# AK-Logger.net
KiCad netlist of a schematic drawn in EAGLE
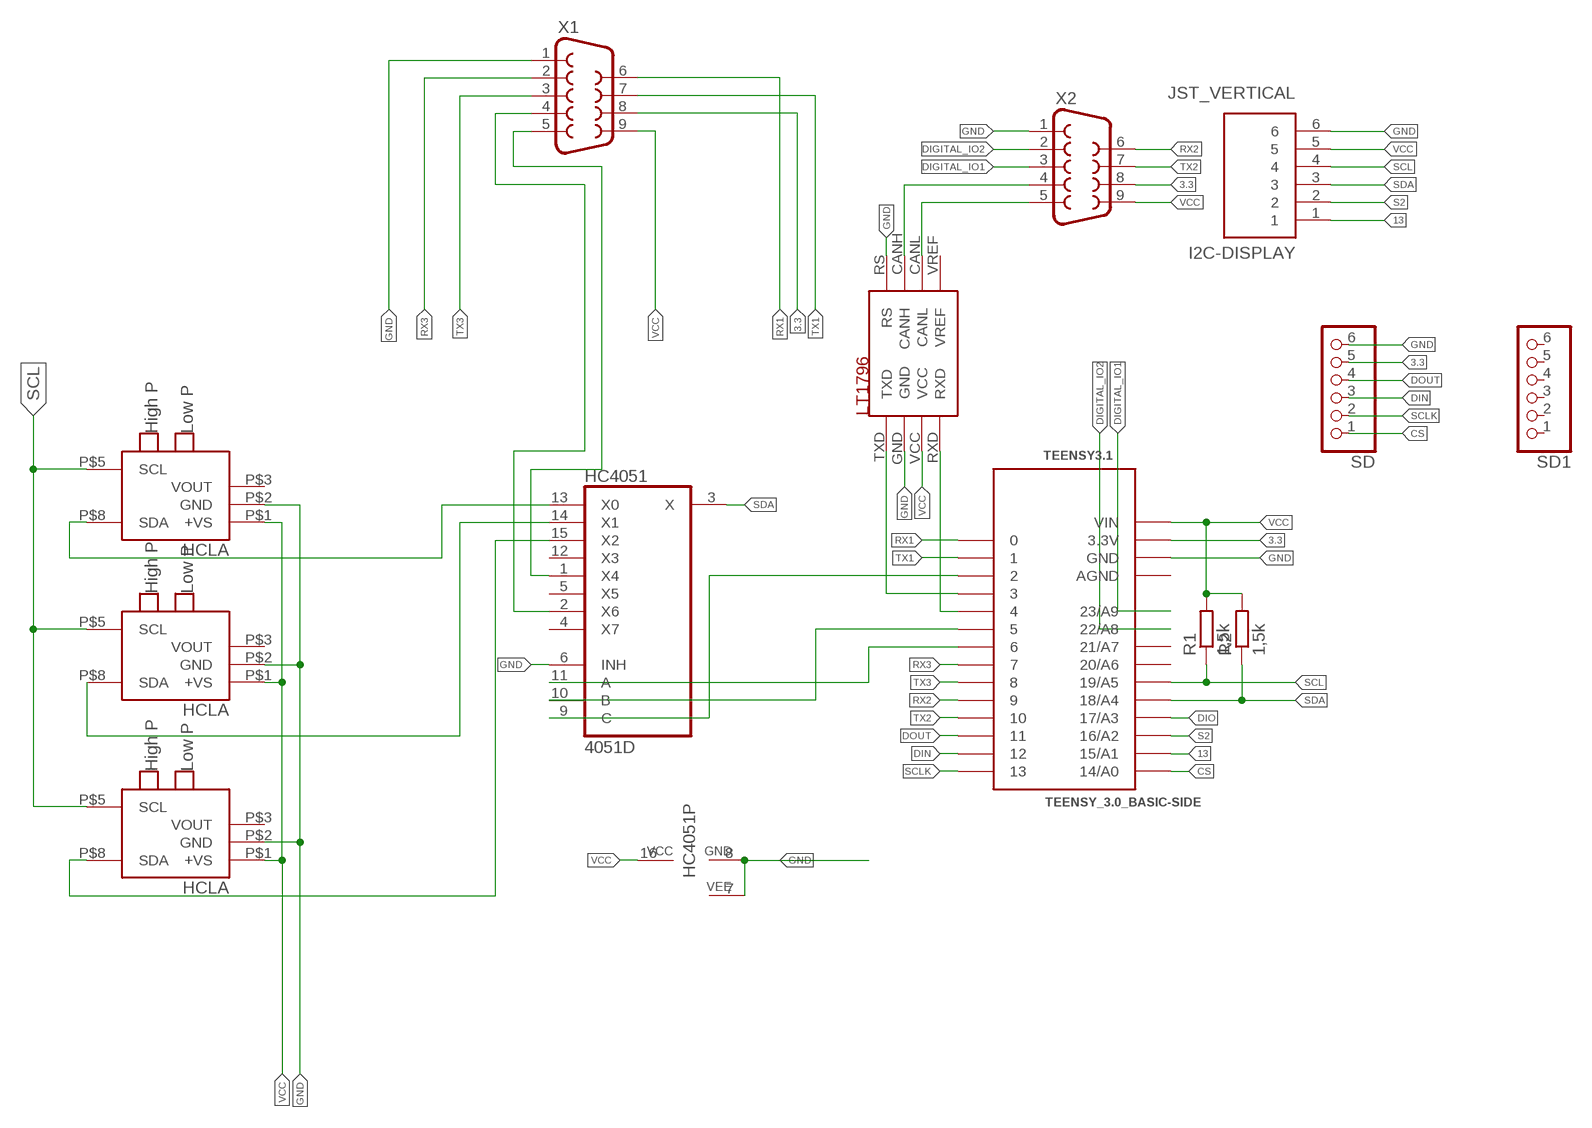
[diagram p0: schematic, sheet 1]

(export (version "E")
  (design (tool "Eeschema 10.0.6"))
  (components
    (comp (ref "HC4051")
      (value "4051D")
      (footprint "eagle-import:SO16")
      (libsource (lib "eagle-import") (part "4051D"))
    )
    (comp (ref "HCLA0")
      (value "HCLA")
      (footprint "eagle-import:HCLA")
      (libsource (lib "eagle-import") (part "HCLA"))
    )
    (comp (ref "HCLA1")
      (value "HCLA")
      (footprint "eagle-import:HCLA")
      (libsource (lib "eagle-import") (part "HCLA"))
    )
    (comp (ref "HCLA2")
      (value "HCLA")
      (footprint "eagle-import:HCLA")
      (libsource (lib "eagle-import") (part "HCLA"))
    )
    (comp (ref "I2C-DISPLAY")
      (value "JST_VERTICAL")
      (footprint "eagle-import:JST-6-SMD-VERT-1.0MM")
      (libsource (lib "eagle-import") (part "JST_VERTICAL"))
    )
    (comp (ref "R1")
      (value "1,5k")
      (footprint "eagle-import:R1206")
      (libsource (lib "eagle-import") (part "R-EU_R1206"))
    )
    (comp (ref "R2")
      (value "1,5k")
      (footprint "eagle-import:R1206")
      (libsource (lib "eagle-import") (part "R-EU_R1206"))
    )
    (comp (ref "SD")
      (value "PINHD-1X6")
      (footprint "eagle-import:1X06")
      (libsource (lib "eagle-import") (part "PINHD-1X6"))
    )
    (comp (ref "SD1")
      (value "PINHD-1X6")
      (footprint "eagle-import:1X06")
      (libsource (lib "eagle-import") (part "PINHD-1X6"))
    )
    (comp (ref "TEENSY3.1")
      (value "TEENSY_3.0_BASIC-SIDE")
      (footprint "eagle-import:TEENSY_3.0_BASIC-SIDE")
      (libsource (lib "eagle-import") (part "TEENSY_3.0_BASIC-SIDE"))
    )
    (comp (ref "U$6")
      (value "LT1796")
      (footprint "eagle-import:SO08")
      (libsource (lib "eagle-import") (part "LT1796"))
    )
    (comp (ref "X1")
      (value "F09H")
      (footprint "eagle-import:F09H")
      (libsource (lib "eagle-import") (part "F09H"))
    )
    (comp (ref "X2")
      (value "F09H")
      (footprint "eagle-import:F09H")
      (libsource (lib "eagle-import") (part "F09H"))
    )
  )
  (nets
    (net (code "1") (name "/AGND") (class "Default")
      (node (ref "TEENSY3.1") (pin "AGND") (pinfunction "AGND_AGND") (pintype "power_in"))
    )
    (net (code "2") (name "3.3") (class "Default")
      (node (ref "SD") (pin "5") (pinfunction "5_5") (pintype "passive"))
      (node (ref "TEENSY3.1") (pin "3.3V") (pinfunction "3.3V_3.3V") (pintype "power_in"))
      (node (ref "X1") (pin "8") (pinfunction "8_8") (pintype "passive"))
      (node (ref "X2") (pin "8") (pinfunction "8_8") (pintype "passive"))
    )
    (net (code "3") (name "13") (class "Default")
      (node (ref "I2C-DISPLAY") (pin "1") (pinfunction "1_1") (pintype "bidirectional"))
      (node (ref "TEENSY3.1") (pin "15/A1") (pinfunction "15/A1_15/A1") (pintype "bidirectional"))
    )
    (net (code "4") (name "CS") (class "Default")
      (node (ref "SD") (pin "1") (pinfunction "1_1") (pintype "passive"))
      (node (ref "TEENSY3.1") (pin "14/A0") (pinfunction "14/A0_14/A0") (pintype "bidirectional"))
    )
    (net (code "5") (name "DIGITAL_IO1") (class "Default")
      (node (ref "TEENSY3.1") (pin "23/A9") (pinfunction "23/A9_23/A9") (pintype "bidirectional"))
      (node (ref "X2") (pin "3") (pinfunction "3_3") (pintype "passive"))
    )
    (net (code "6") (name "DIGITAL_IO2") (class "Default")
      (node (ref "TEENSY3.1") (pin "22/A8") (pinfunction "22/A8_22/A8") (pintype "bidirectional"))
      (node (ref "X2") (pin "2") (pinfunction "2_2") (pintype "passive"))
    )
    (net (code "7") (name "DIN") (class "Default")
      (node (ref "SD") (pin "3") (pinfunction "3_3") (pintype "passive"))
      (node (ref "TEENSY3.1") (pin "12") (pinfunction "12_12") (pintype "bidirectional"))
    )
    (net (code "8") (name "DIO") (class "Default")
      (node (ref "TEENSY3.1") (pin "17/A3") (pinfunction "17/A3_17/A3") (pintype "bidirectional"))
    )
    (net (code "9") (name "DOUT") (class "Default")
      (node (ref "SD") (pin "4") (pinfunction "4_4") (pintype "passive"))
      (node (ref "TEENSY3.1") (pin "11") (pinfunction "11_11") (pintype "bidirectional"))
    )
    (net (code "10") (name "GND") (class "Default")
      (node (ref "HC4051") (pin "6") (pinfunction "INH_6") (pintype "input"))
      (node (ref "HC4051") (pin "7") (pinfunction "VEE_7") (pintype "power_in"))
      (node (ref "HC4051") (pin "8") (pinfunction "GND_8") (pintype "power_in"))
      (node (ref "HCLA0") (pin "P$2") (pinfunction "GND_P$2") (pintype "bidirectional"))
      (node (ref "HCLA1") (pin "P$2") (pinfunction "GND_P$2") (pintype "bidirectional"))
      (node (ref "HCLA2") (pin "P$2") (pinfunction "GND_P$2") (pintype "bidirectional"))
      (node (ref "I2C-DISPLAY") (pin "6") (pinfunction "6_6") (pintype "bidirectional"))
      (node (ref "SD") (pin "6") (pinfunction "6_6") (pintype "passive"))
      (node (ref "TEENSY3.1") (pin "GND") (pinfunction "GND_GND") (pintype "power_in"))
      (node (ref "U$6") (pin "GND") (pinfunction "GND_GND") (pintype "bidirectional"))
      (node (ref "U$6") (pin "RS") (pinfunction "RS_RS") (pintype "bidirectional"))
      (node (ref "X1") (pin "1") (pinfunction "1_1") (pintype "passive"))
      (node (ref "X2") (pin "1") (pinfunction "1_1") (pintype "passive"))
    )
    (net (code "11") (name "Net-(HC4051A-A)") (class "Default")
      (node (ref "HC4051") (pin "11") (pinfunction "A_11") (pintype "input"))
      (node (ref "TEENSY3.1") (pin "6") (pinfunction "6_6") (pintype "bidirectional"))
    )
    (net (code "12") (name "Net-(HC4051A-B)") (class "Default")
      (node (ref "HC4051") (pin "10") (pinfunction "B_10") (pintype "input"))
      (node (ref "TEENSY3.1") (pin "5") (pinfunction "5_5") (pintype "bidirectional"))
    )
    (net (code "13") (name "Net-(HC4051A-C)") (class "Default")
      (node (ref "HC4051") (pin "9") (pinfunction "C_9") (pintype "input"))
      (node (ref "TEENSY3.1") (pin "2") (pinfunction "2_2") (pintype "bidirectional"))
    )
    (net (code "14") (name "Net-(HC4051A-X0)") (class "Default")
      (node (ref "HC4051") (pin "13") (pinfunction "X0_13") (pintype "bidirectional"))
      (node (ref "HCLA0") (pin "P$8") (pinfunction "SDA_P$8") (pintype "bidirectional"))
    )
    (net (code "15") (name "Net-(HC4051A-X1)") (class "Default")
      (node (ref "HC4051") (pin "14") (pinfunction "X1_14") (pintype "bidirectional"))
      (node (ref "HCLA1") (pin "P$8") (pinfunction "SDA_P$8") (pintype "bidirectional"))
    )
    (net (code "16") (name "Net-(HC4051A-X2)") (class "Default")
      (node (ref "HC4051") (pin "15") (pinfunction "X2_15") (pintype "bidirectional"))
      (node (ref "HCLA2") (pin "P$8") (pinfunction "SDA_P$8") (pintype "bidirectional"))
    )
    (net (code "17") (name "Net-(HC4051A-X4)") (class "Default")
      (node (ref "HC4051") (pin "1") (pinfunction "X4_1") (pintype "bidirectional"))
      (node (ref "X1") (pin "5") (pinfunction "5_5") (pintype "passive"))
    )
    (net (code "18") (name "Net-(HC4051A-X6)") (class "Default")
      (node (ref "HC4051") (pin "2") (pinfunction "X6_2") (pintype "bidirectional"))
      (node (ref "X1") (pin "4") (pinfunction "4_4") (pintype "passive"))
    )
    (net (code "19") (name "Net-(TEENSY3.1-Pad3)") (class "Default")
      (node (ref "TEENSY3.1") (pin "3") (pinfunction "3_3") (pintype "bidirectional"))
      (node (ref "U$6") (pin "TXD") (pinfunction "TXD_TXD") (pintype "bidirectional"))
    )
    (net (code "20") (name "Net-(TEENSY3.1-Pad4)") (class "Default")
      (node (ref "TEENSY3.1") (pin "4") (pinfunction "4_4") (pintype "bidirectional"))
      (node (ref "U$6") (pin "RXD") (pinfunction "RXD_RXD") (pintype "bidirectional"))
    )
    (net (code "21") (name "Net-(U$6-PadCANH)") (class "Default")
      (node (ref "U$6") (pin "CANH") (pinfunction "CANH_CANH") (pintype "bidirectional"))
      (node (ref "X2") (pin "4") (pinfunction "4_4") (pintype "passive"))
    )
    (net (code "22") (name "Net-(U$6-PadCANL)") (class "Default")
      (node (ref "U$6") (pin "CANL") (pinfunction "CANL_CANL") (pintype "bidirectional"))
      (node (ref "X2") (pin "5") (pinfunction "5_5") (pintype "passive"))
    )
    (net (code "23") (name "RX1") (class "Default")
      (node (ref "TEENSY3.1") (pin "0") (pinfunction "0_0") (pintype "bidirectional"))
      (node (ref "X1") (pin "6") (pinfunction "6_6") (pintype "passive"))
    )
    (net (code "24") (name "RX2") (class "Default")
      (node (ref "TEENSY3.1") (pin "9") (pinfunction "9_9") (pintype "bidirectional"))
      (node (ref "X2") (pin "6") (pinfunction "6_6") (pintype "passive"))
    )
    (net (code "25") (name "RX3") (class "Default")
      (node (ref "TEENSY3.1") (pin "7") (pinfunction "7_7") (pintype "bidirectional"))
      (node (ref "X1") (pin "2") (pinfunction "2_2") (pintype "passive"))
    )
    (net (code "26") (name "S2") (class "Default")
      (node (ref "I2C-DISPLAY") (pin "2") (pinfunction "2_2") (pintype "bidirectional"))
      (node (ref "TEENSY3.1") (pin "16/A2") (pinfunction "16/A2_16/A2") (pintype "bidirectional"))
    )
    (net (code "27") (name "SCL") (class "Default")
      (node (ref "HCLA0") (pin "P$5") (pinfunction "SCL_P$5") (pintype "bidirectional"))
      (node (ref "HCLA1") (pin "P$5") (pinfunction "SCL_P$5") (pintype "bidirectional"))
      (node (ref "HCLA2") (pin "P$5") (pinfunction "SCL_P$5") (pintype "bidirectional"))
      (node (ref "I2C-DISPLAY") (pin "4") (pinfunction "4_4") (pintype "bidirectional"))
      (node (ref "R1") (pin "1") (pinfunction "1_1") (pintype "passive"))
      (node (ref "TEENSY3.1") (pin "19/A5") (pinfunction "19/A5_19/A5") (pintype "bidirectional"))
    )
    (net (code "28") (name "SCLK") (class "Default")
      (node (ref "SD") (pin "2") (pinfunction "2_2") (pintype "passive"))
      (node (ref "TEENSY3.1") (pin "13") (pinfunction "13_13") (pintype "bidirectional"))
    )
    (net (code "29") (name "SDA") (class "Default")
      (node (ref "HC4051") (pin "3") (pinfunction "X_3") (pintype "bidirectional"))
      (node (ref "I2C-DISPLAY") (pin "3") (pinfunction "3_3") (pintype "bidirectional"))
      (node (ref "R2") (pin "1") (pinfunction "1_1") (pintype "passive"))
      (node (ref "TEENSY3.1") (pin "18/A4") (pinfunction "18/A4_18/A4") (pintype "bidirectional"))
    )
    (net (code "30") (name "TX1") (class "Default")
      (node (ref "TEENSY3.1") (pin "1") (pinfunction "1_1") (pintype "bidirectional"))
      (node (ref "X1") (pin "7") (pinfunction "7_7") (pintype "passive"))
    )
    (net (code "31") (name "TX2") (class "Default")
      (node (ref "TEENSY3.1") (pin "10") (pinfunction "10_10") (pintype "bidirectional"))
      (node (ref "X2") (pin "7") (pinfunction "7_7") (pintype "passive"))
    )
    (net (code "32") (name "TX3") (class "Default")
      (node (ref "TEENSY3.1") (pin "8") (pinfunction "8_8") (pintype "bidirectional"))
      (node (ref "X1") (pin "3") (pinfunction "3_3") (pintype "passive"))
    )
    (net (code "33") (name "VCC") (class "Default")
      (node (ref "HC4051") (pin "16") (pinfunction "VCC_16") (pintype "power_in"))
      (node (ref "HCLA0") (pin "P$1") (pinfunction "+VS_P$1") (pintype "bidirectional"))
      (node (ref "HCLA1") (pin "P$1") (pinfunction "+VS_P$1") (pintype "bidirectional"))
      (node (ref "HCLA2") (pin "P$1") (pinfunction "+VS_P$1") (pintype "bidirectional"))
      (node (ref "I2C-DISPLAY") (pin "5") (pinfunction "5_5") (pintype "bidirectional"))
      (node (ref "R1") (pin "2") (pinfunction "2_2") (pintype "passive"))
      (node (ref "R2") (pin "2") (pinfunction "2_2") (pintype "passive"))
      (node (ref "TEENSY3.1") (pin "VIN") (pinfunction "VIN_VIN") (pintype "power_in"))
      (node (ref "U$6") (pin "VCC") (pinfunction "VCC_VCC") (pintype "bidirectional"))
      (node (ref "X1") (pin "9") (pinfunction "9_9") (pintype "passive"))
      (node (ref "X2") (pin "9") (pinfunction "9_9") (pintype "passive"))
    )
    (net (code "34") (name "unconnected-(HC4051A-X3-Pad12)") (class "Default")
      (node (ref "HC4051") (pin "12") (pinfunction "X3_12") (pintype "bidirectional"))
    )
    (net (code "35") (name "unconnected-(HC4051A-X5-Pad5)") (class "Default")
      (node (ref "HC4051") (pin "5") (pinfunction "X5_5") (pintype "bidirectional"))
    )
    (net (code "36") (name "unconnected-(HC4051A-X7-Pad4)") (class "Default")
      (node (ref "HC4051") (pin "4") (pinfunction "X7_4") (pintype "bidirectional"))
    )
    (net (code "37") (name "unconnected-(HCLA0-VOUT-PadP$3)") (class "Default")
      (node (ref "HCLA0") (pin "P$3") (pinfunction "VOUT_P$3") (pintype "bidirectional"))
    )
    (net (code "38") (name "unconnected-(HCLA1-VOUT-PadP$3)") (class "Default")
      (node (ref "HCLA1") (pin "P$3") (pinfunction "VOUT_P$3") (pintype "bidirectional"))
    )
    (net (code "39") (name "unconnected-(HCLA2-VOUT-PadP$3)") (class "Default")
      (node (ref "HCLA2") (pin "P$3") (pinfunction "VOUT_P$3") (pintype "bidirectional"))
    )
    (net (code "40") (name "unconnected-(SD1-Pad1)") (class "Default")
      (node (ref "SD1") (pin "1") (pinfunction "1_1") (pintype "passive"))
    )
    (net (code "41") (name "unconnected-(SD1-Pad2)") (class "Default")
      (node (ref "SD1") (pin "2") (pinfunction "2_2") (pintype "passive"))
    )
    (net (code "42") (name "unconnected-(SD1-Pad3)") (class "Default")
      (node (ref "SD1") (pin "3") (pinfunction "3_3") (pintype "passive"))
    )
    (net (code "43") (name "unconnected-(SD1-Pad4)") (class "Default")
      (node (ref "SD1") (pin "4") (pinfunction "4_4") (pintype "passive"))
    )
    (net (code "44") (name "unconnected-(SD1-Pad5)") (class "Default")
      (node (ref "SD1") (pin "5") (pinfunction "5_5") (pintype "passive"))
    )
    (net (code "45") (name "unconnected-(SD1-Pad6)") (class "Default")
      (node (ref "SD1") (pin "6") (pinfunction "6_6") (pintype "passive"))
    )
    (net (code "46") (name "unconnected-(TEENSY3.1-Pad20{slash}A6)") (class "Default")
      (node (ref "TEENSY3.1") (pin "20/A6") (pinfunction "20/A6_20/A6") (pintype "bidirectional"))
    )
    (net (code "47") (name "unconnected-(TEENSY3.1-Pad21{slash}A7)") (class "Default")
      (node (ref "TEENSY3.1") (pin "21/A7") (pinfunction "21/A7_21/A7") (pintype "bidirectional"))
    )
    (net (code "48") (name "unconnected-(U$6-PadVREF)") (class "Default")
      (node (ref "U$6") (pin "VREF") (pinfunction "VREF_VREF") (pintype "bidirectional"))
    )
  )
)
